# Top.net
KiCad netlist of a schematic drawn in Altium Designer
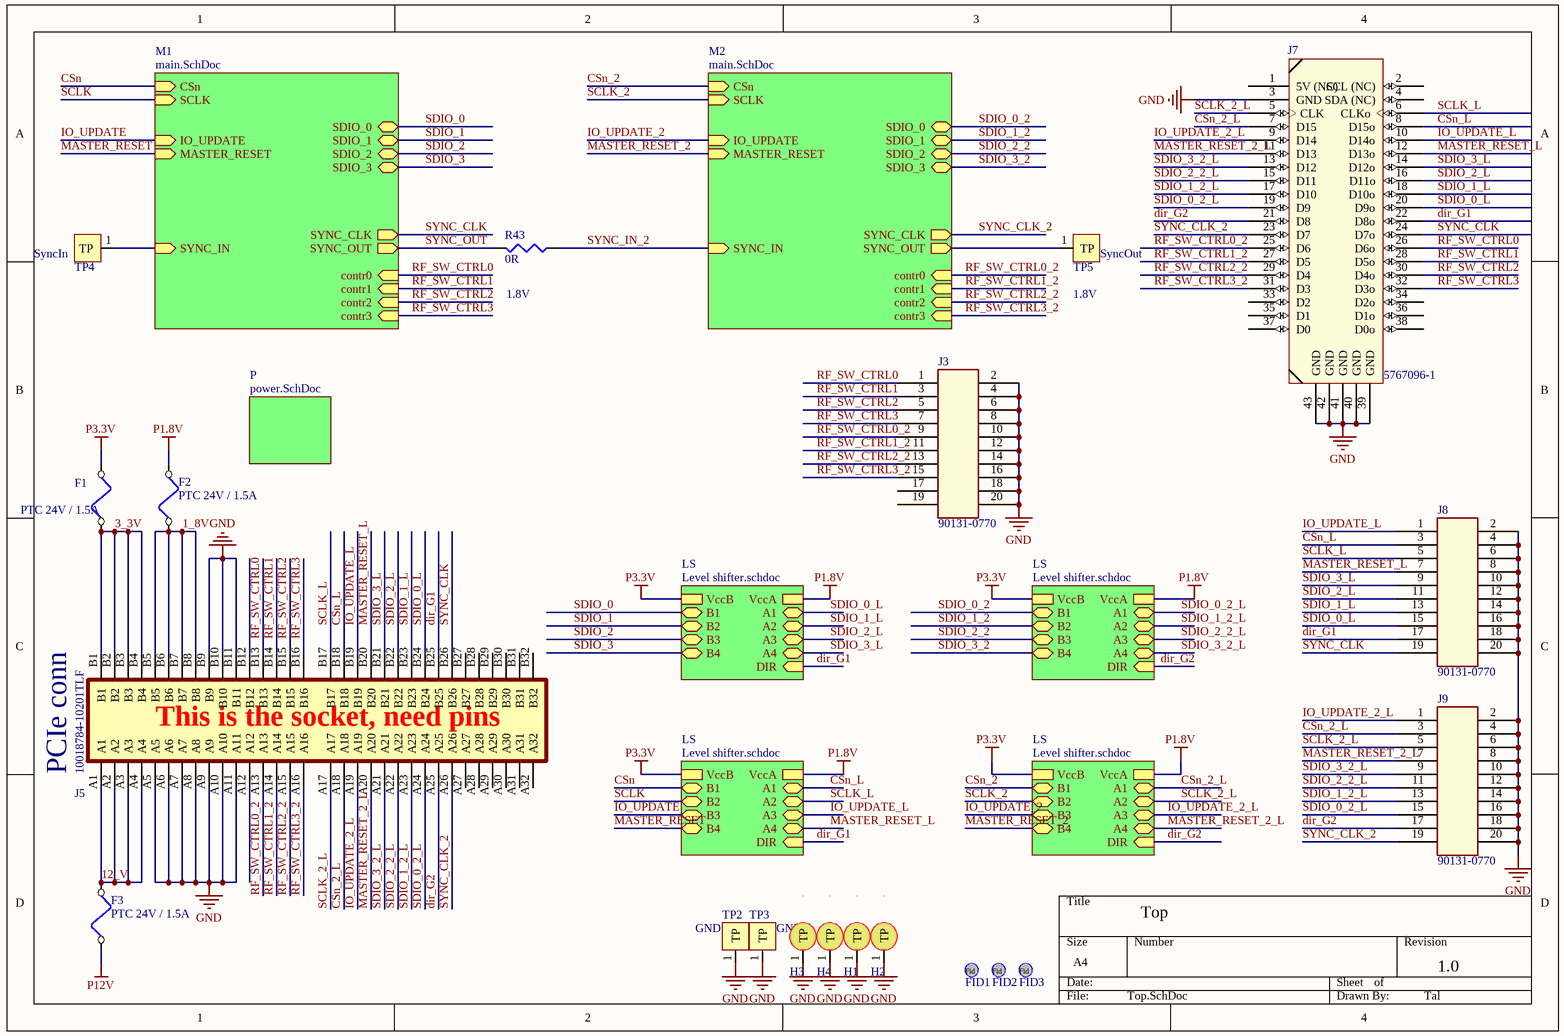
[diagram p0: Top.SchDoc]

(export (version "E")
  (design (tool "Eeschema 10.0.6"))
  (components
    (comp (ref "F1")
      (value "PTC 24V / 1.5A")
      (footprint "Landa_PCB:1812_F")
      (description "FUSE PTC 24V 1.5A POLYFUSE 1812")
      (fields
        (field (name "MANUFACTURER") "Littelfuse Inc")
        (field (name "MANUFACTURER PART NUMBER") "1812L150/24MR")
      )
      (libsource (lib "DPB_spliter") (part "1812L150/24MR"))
    )
    (comp (ref "F2")
      (value "PTC 24V / 1.5A")
      (footprint "Landa_PCB:1812_F")
      (description "FUSE PTC 24V 1.5A POLYFUSE 1812")
      (fields
        (field (name "MANUFACTURER") "Littelfuse Inc")
        (field (name "MANUFACTURER PART NUMBER") "1812L150/24MR")
      )
      (libsource (lib "DPB_spliter") (part "1812L150/24MR"))
    )
    (comp (ref "F3")
      (value "PTC 24V / 1.5A")
      (footprint "Landa_PCB:1812_F")
      (description "FUSE PTC 24V 1.5A POLYFUSE 1812")
      (fields
        (field (name "MANUFACTURER") "Littelfuse Inc")
        (field (name "MANUFACTURER PART NUMBER") "1812L150/24MR")
      )
      (libsource (lib "DPB_spliter") (part "1812L150/24MR"))
    )
    (comp (ref "FID1")
      (value "Fiducial")
      (footprint "Fiducial")
      (libsource (lib "DDS_PCB") (part "Fiducial"))
    )
    (comp (ref "FID2")
      (value "Fiducial")
      (footprint "Fiducial")
      (libsource (lib "DDS_PCB") (part "Fiducial"))
    )
    (comp (ref "FID3")
      (value "Fiducial")
      (footprint "Fiducial")
      (libsource (lib "DDS_PCB") (part "Fiducial"))
    )
    (comp (ref "H1")
      (value "Hole 3mm")
      (footprint "hole 3mm")
      (description "hole 3mm")
      (libsource (lib "L_SCH_Misc") (part "Hole 3mm"))
    )
    (comp (ref "H2")
      (value "Hole 3mm")
      (footprint "hole 3mm")
      (description "hole 3mm")
      (libsource (lib "L_SCH_Misc") (part "Hole 3mm"))
    )
    (comp (ref "H3")
      (value "Hole 3mm")
      (footprint "hole 3mm")
      (description "hole 3mm")
      (libsource (lib "L_SCH_Misc") (part "Hole 3mm"))
    )
    (comp (ref "H4")
      (value "Hole 3mm")
      (footprint "hole 3mm")
      (description "hole 3mm")
      (libsource (lib "L_SCH_Misc") (part "Hole 3mm"))
    )
    (comp (ref "J3")
      (value "90131-0770")
      (footprint "HEADER_10x2")
      (description "CONN HEADER 20 TH")
      (fields
        (field (name "MANUFACTURER") "Molex Connector Corporation")
        (field (name "MANUFACTURER PART NUMBER") "90131-0770")
      )
      (libsource (lib "L_SCH_J_Z") (part "90131-0770"))
    )
    (comp (ref "J5")
      (value "10018784-10201TLF")
      (footprint "CONN_10018784-10201TLF")
      (description "64 Position Female Connector PCI Expressâ„¢ Gold 0.039 _1.00mm_ Black")
      (fields (field (name "MF") "Amphenol ICC"))
      (libsource (lib "10018784-10201TLF") (part "10018784-10201TLF"))
    )
    (comp (ref "J7")
      (value "5767096-1")
      (footprint "MICTOR-38_PIN")
      (description "CONN MICTOR 38POS .025 VERT SMD")
      (fields
        (field (name "MANUFACTURER") "TE Connectivity")
        (field (name "MANUFACTURER PART NUMBER") "5767096-1")
      )
      (libsource (lib "L_SCH_J_Z") (part "5767096-1"))
    )
    (comp (ref "J8")
      (value "90131-0770")
      (footprint "HEADER_10x2")
      (description "CONN HEADER 20 TH")
      (fields
        (field (name "MANUFACTURER") "Molex Connector Corporation")
        (field (name "MANUFACTURER PART NUMBER") "90131-0770")
      )
      (libsource (lib "L_SCH_J_Z") (part "90131-0770"))
    )
    (comp (ref "J9")
      (value "90131-0770")
      (footprint "HEADER_10x2")
      (description "CONN HEADER 20 TH")
      (fields
        (field (name "MANUFACTURER") "Molex Connector Corporation")
        (field (name "MANUFACTURER PART NUMBER") "90131-0770")
      )
      (libsource (lib "L_SCH_J_Z") (part "90131-0770"))
    )
    (comp (ref "R43")
      (value "0R")
      (footprint "R0402")
      (description "RES 0 OHM 1/10W 1% 0402 SMD")
      (fields
        (field (name "MANUFACTURER PART NUMBER") "ERJ-2RKF1000X")
        (field (name "MANUFACTURER") "Panasonic Electronic Components")
      )
      (libsource (lib "L_SCH_R") (part "RES 100 OHM 1/10W 1% 0402 SMD"))
    )
    (comp (ref "TP2")
      (value "GND")
      (footprint "Landa_PCB:TP_2x1.8")
      (description "TP PC MINIATURE SMT")
      (fields
        (field (name "MANUFACTURER") "Keystone Electronics")
        (field (name "MANUFACTURER PART NUMBER") "5015")
      )
      (libsource (lib "") (part "TP mini_2_2"))
    )
    (comp (ref "TP3")
      (value "GND")
      (footprint "Landa_PCB:TP_2x1.8")
      (description "TP PC MINIATURE SMT")
      (fields
        (field (name "MANUFACTURER") "Keystone Electronics")
        (field (name "MANUFACTURER PART NUMBER") "5015")
      )
      (libsource (lib "DPB_spliter") (part "TP mini_1"))
    )
    (comp (ref "TP4")
      (value "SyncIn")
      (footprint "Landa_PCB:TP_2x1.8")
      (description "TP PC MINIATURE SMT")
      (fields
        (field (name "MANUFACTURER") "Keystone Electronics")
        (field (name "MANUFACTURER PART NUMBER") "5015")
      )
      (libsource (lib "DPB_spliter") (part "TP mini_2"))
    )
    (comp (ref "TP5")
      (value "SyncOut")
      (footprint "Landa_PCB:TP_2x1.8")
      (description "TP PC MINIATURE SMT")
      (fields
        (field (name "MANUFACTURER") "Keystone Electronics")
        (field (name "MANUFACTURER PART NUMBER") "5015")
      )
      (libsource (lib "") (part "TP mini_2_1"))
    )
  )
  (nets
    (net (code "1") (name "/1_8V") (class "Default")
      (node (ref "F2") (pin "1") (pinfunction "1_1") (pintype "passive"))
      (node (ref "J5") (pin "B5") (pinfunction "B5_B5") (pintype "passive"))
      (node (ref "J5") (pin "B6") (pinfunction "B6_B6") (pintype "passive"))
      (node (ref "J5") (pin "B7") (pinfunction "B7_B7") (pintype "passive"))
      (node (ref "J5") (pin "B8") (pinfunction "B8_B8") (pintype "passive"))
    )
    (net (code "2") (name "/3_3V") (class "Default")
      (node (ref "F1") (pin "1") (pinfunction "1_1") (pintype "passive"))
      (node (ref "J5") (pin "B1") (pinfunction "B1_B1") (pintype "passive"))
      (node (ref "J5") (pin "B2") (pinfunction "B2_B2") (pintype "passive"))
      (node (ref "J5") (pin "B3") (pinfunction "B3_B3") (pintype "passive"))
      (node (ref "J5") (pin "B4") (pinfunction "B4_B4") (pintype "passive"))
    )
    (net (code "3") (name "/12_V") (class "Default")
      (node (ref "F3") (pin "2") (pinfunction "2_2") (pintype "passive"))
      (node (ref "J5") (pin "A1") (pinfunction "A1_A1") (pintype "passive"))
      (node (ref "J5") (pin "A2") (pinfunction "A2_A2") (pintype "passive"))
      (node (ref "J5") (pin "A3") (pinfunction "A3_A3") (pintype "passive"))
      (node (ref "J5") (pin "A4") (pinfunction "A4_A4") (pintype "passive"))
    )
    (net (code "6") (name "/CSn_2_L") (class "Default")
      (node (ref "J5") (pin "A18") (pinfunction "A18_A18") (pintype "passive"))
      (node (ref "J7") (pin "7") (pinfunction "D15_7") (pintype "bidirectional"))
      (node (ref "J9") (pin "3") (pinfunction "3_3") (pintype "passive"))
    )
    (net (code "7") (name "/CSn_L") (class "Default")
      (node (ref "J5") (pin "B18") (pinfunction "B18_B18") (pintype "passive"))
      (node (ref "J7") (pin "8") (pinfunction "D15o_8") (pintype "bidirectional"))
      (node (ref "J8") (pin "3") (pinfunction "3_3") (pintype "passive"))
    )
    (net (code "10") (name "/IO_UPDATE_2_L") (class "Default")
      (node (ref "J5") (pin "A19") (pinfunction "A19_A19") (pintype "passive"))
      (node (ref "J7") (pin "9") (pinfunction "D14_9") (pintype "bidirectional"))
      (node (ref "J9") (pin "1") (pinfunction "1_1") (pintype "passive"))
    )
    (net (code "11") (name "/IO_UPDATE_L") (class "Default")
      (node (ref "J5") (pin "B19") (pinfunction "B19_B19") (pintype "passive"))
      (node (ref "J7") (pin "10") (pinfunction "D14o_10") (pintype "bidirectional"))
      (node (ref "J8") (pin "1") (pinfunction "1_1") (pintype "passive"))
    )
    (net (code "14") (name "/MASTER_RESET_2_L") (class "Default")
      (node (ref "J5") (pin "A20") (pinfunction "A20_A20") (pintype "passive"))
      (node (ref "J7") (pin "11") (pinfunction "D13_11") (pintype "bidirectional"))
      (node (ref "J9") (pin "7") (pinfunction "7_7") (pintype "passive"))
    )
    (net (code "15") (name "/MASTER_RESET_L") (class "Default")
      (node (ref "J5") (pin "B20") (pinfunction "B20_B20") (pintype "passive"))
      (node (ref "J7") (pin "12") (pinfunction "D13o_12") (pintype "bidirectional"))
      (node (ref "J8") (pin "7") (pinfunction "7_7") (pintype "passive"))
    )
    (net (code "16") (name "/RF_SW_CTRL0") (class "Default")
      (node (ref "J3") (pin "1") (pinfunction "1_1") (pintype "passive"))
      (node (ref "J5") (pin "B13") (pinfunction "B13_B13") (pintype "passive"))
      (node (ref "J7") (pin "26") (pinfunction "D6o_26") (pintype "bidirectional"))
    )
    (net (code "17") (name "/RF_SW_CTRL0_2") (class "Default")
      (node (ref "J3") (pin "9") (pinfunction "9_9") (pintype "passive"))
      (node (ref "J5") (pin "A13") (pinfunction "A13_A13") (pintype "passive"))
      (node (ref "J7") (pin "25") (pinfunction "D6_25") (pintype "bidirectional"))
    )
    (net (code "18") (name "/RF_SW_CTRL1") (class "Default")
      (node (ref "J3") (pin "3") (pinfunction "3_3") (pintype "passive"))
      (node (ref "J5") (pin "B14") (pinfunction "B14_B14") (pintype "passive"))
      (node (ref "J7") (pin "28") (pinfunction "D5o_28") (pintype "bidirectional"))
    )
    (net (code "19") (name "/RF_SW_CTRL1_2") (class "Default")
      (node (ref "J3") (pin "11") (pinfunction "11_11") (pintype "passive"))
      (node (ref "J5") (pin "A14") (pinfunction "A14_A14") (pintype "passive"))
      (node (ref "J7") (pin "27") (pinfunction "D5_27") (pintype "bidirectional"))
    )
    (net (code "20") (name "/RF_SW_CTRL2") (class "Default")
      (node (ref "J3") (pin "5") (pinfunction "5_5") (pintype "passive"))
      (node (ref "J5") (pin "B15") (pinfunction "B15_B15") (pintype "passive"))
      (node (ref "J7") (pin "30") (pinfunction "D4o_30") (pintype "bidirectional"))
    )
    (net (code "21") (name "/RF_SW_CTRL2_2") (class "Default")
      (node (ref "J3") (pin "13") (pinfunction "13_13") (pintype "passive"))
      (node (ref "J5") (pin "A15") (pinfunction "A15_A15") (pintype "passive"))
      (node (ref "J7") (pin "29") (pinfunction "D4_29") (pintype "bidirectional"))
    )
    (net (code "22") (name "/RF_SW_CTRL3") (class "Default")
      (node (ref "J3") (pin "7") (pinfunction "7_7") (pintype "passive"))
      (node (ref "J5") (pin "B16") (pinfunction "B16_B16") (pintype "passive"))
      (node (ref "J7") (pin "32") (pinfunction "D3o_32") (pintype "bidirectional"))
    )
    (net (code "23") (name "/RF_SW_CTRL3_2") (class "Default")
      (node (ref "J3") (pin "15") (pinfunction "15_15") (pintype "passive"))
      (node (ref "J5") (pin "A16") (pinfunction "A16_A16") (pintype "passive"))
      (node (ref "J7") (pin "31") (pinfunction "D3_31") (pintype "bidirectional"))
    )
    (net (code "26") (name "/SCLK_2_L") (class "Default")
      (node (ref "J5") (pin "A17") (pinfunction "A17_A17") (pintype "passive"))
      (node (ref "J7") (pin "5") (pinfunction "CLK_5") (pintype "bidirectional"))
      (node (ref "J9") (pin "5") (pinfunction "5_5") (pintype "passive"))
    )
    (net (code "27") (name "/SCLK_L") (class "Default")
      (node (ref "J5") (pin "B17") (pinfunction "B17_B17") (pintype "passive"))
      (node (ref "J7") (pin "6") (pinfunction "CLKo_6") (pintype "bidirectional"))
      (node (ref "J8") (pin "5") (pinfunction "5_5") (pintype "passive"))
    )
    (net (code "30") (name "/SDIO_0_2_L") (class "Default")
      (node (ref "J5") (pin "A24") (pinfunction "A24_A24") (pintype "passive"))
      (node (ref "J7") (pin "19") (pinfunction "D9_19") (pintype "bidirectional"))
      (node (ref "J9") (pin "15") (pinfunction "15_15") (pintype "passive"))
    )
    (net (code "31") (name "/SDIO_0_L") (class "Default")
      (node (ref "J5") (pin "B24") (pinfunction "B24_B24") (pintype "passive"))
      (node (ref "J7") (pin "20") (pinfunction "D9o_20") (pintype "bidirectional"))
      (node (ref "J8") (pin "15") (pinfunction "15_15") (pintype "passive"))
    )
    (net (code "34") (name "/SDIO_1_2_L") (class "Default")
      (node (ref "J5") (pin "A23") (pinfunction "A23_A23") (pintype "passive"))
      (node (ref "J7") (pin "17") (pinfunction "D10_17") (pintype "bidirectional"))
      (node (ref "J9") (pin "13") (pinfunction "13_13") (pintype "passive"))
    )
    (net (code "35") (name "/SDIO_1_L") (class "Default")
      (node (ref "J5") (pin "B23") (pinfunction "B23_B23") (pintype "passive"))
      (node (ref "J7") (pin "18") (pinfunction "D10o_18") (pintype "bidirectional"))
      (node (ref "J8") (pin "13") (pinfunction "13_13") (pintype "passive"))
    )
    (net (code "38") (name "/SDIO_2_2_L") (class "Default")
      (node (ref "J5") (pin "A22") (pinfunction "A22_A22") (pintype "passive"))
      (node (ref "J7") (pin "15") (pinfunction "D11_15") (pintype "bidirectional"))
      (node (ref "J9") (pin "11") (pinfunction "11_11") (pintype "passive"))
    )
    (net (code "39") (name "/SDIO_2_L") (class "Default")
      (node (ref "J5") (pin "B22") (pinfunction "B22_B22") (pintype "passive"))
      (node (ref "J7") (pin "16") (pinfunction "D11o_16") (pintype "bidirectional"))
      (node (ref "J8") (pin "11") (pinfunction "11_11") (pintype "passive"))
    )
    (net (code "42") (name "/SDIO_3_2_L") (class "Default")
      (node (ref "J5") (pin "A21") (pinfunction "A21_A21") (pintype "passive"))
      (node (ref "J7") (pin "13") (pinfunction "D12_13") (pintype "bidirectional"))
      (node (ref "J9") (pin "9") (pinfunction "9_9") (pintype "passive"))
    )
    (net (code "43") (name "/SDIO_3_L") (class "Default")
      (node (ref "J5") (pin "B21") (pinfunction "B21_B21") (pintype "passive"))
      (node (ref "J7") (pin "14") (pinfunction "D12o_14") (pintype "bidirectional"))
      (node (ref "J8") (pin "9") (pinfunction "9_9") (pintype "passive"))
    )
    (net (code "44") (name "/SYNC_CLK") (class "Default")
      (node (ref "J5") (pin "B26") (pinfunction "B26_B26") (pintype "passive"))
      (node (ref "J7") (pin "24") (pinfunction "D7o_24") (pintype "bidirectional"))
      (node (ref "J8") (pin "19") (pinfunction "19_19") (pintype "passive"))
    )
    (net (code "45") (name "/SYNC_CLK_2") (class "Default")
      (node (ref "J5") (pin "A26") (pinfunction "A26_A26") (pintype "passive"))
      (node (ref "J7") (pin "23") (pinfunction "D7_23") (pintype "bidirectional"))
      (node (ref "J9") (pin "19") (pinfunction "19_19") (pintype "passive"))
    )
    (net (code "46") (name "/SYNC_IN") (class "Default")
      (node (ref "TP4") (pin "1") (pinfunction "TP_1") (pintype "passive"))
    )
    (net (code "47") (name "/SYNC_IN_2") (class "Default")
      (node (ref "R43") (pin "1") (pinfunction "1_1") (pintype "passive"))
    )
    (net (code "48") (name "/SYNC_OUT") (class "Default")
      (node (ref "R43") (pin "2") (pinfunction "2_2") (pintype "passive"))
    )
    (net (code "49") (name "/SYNC_OUT_1") (class "Default")
      (node (ref "TP5") (pin "1") (pinfunction "TP_1") (pintype "passive"))
    )
    (net (code "50") (name "/dir_G1") (class "Default")
      (node (ref "J5") (pin "B25") (pinfunction "B25_B25") (pintype "passive"))
      (node (ref "J7") (pin "22") (pinfunction "D8o_22") (pintype "bidirectional"))
      (node (ref "J8") (pin "17") (pinfunction "17_17") (pintype "passive"))
    )
    (net (code "51") (name "/dir_G2") (class "Default")
      (node (ref "J5") (pin "A25") (pinfunction "A25_A25") (pintype "passive"))
      (node (ref "J7") (pin "21") (pinfunction "D8_21") (pintype "bidirectional"))
      (node (ref "J9") (pin "17") (pinfunction "17_17") (pintype "passive"))
    )
    (net (code "52") (name "GND") (class "Default")
      (node (ref "H1") (pin "1") (pinfunction "TP_1") (pintype "passive"))
      (node (ref "H2") (pin "1") (pinfunction "TP_1") (pintype "passive"))
      (node (ref "H3") (pin "1") (pinfunction "TP_1") (pintype "passive"))
      (node (ref "H4") (pin "1") (pinfunction "TP_1") (pintype "passive"))
      (node (ref "J3") (pin "10") (pinfunction "10_10") (pintype "passive"))
      (node (ref "J3") (pin "12") (pinfunction "12_12") (pintype "passive"))
      (node (ref "J3") (pin "14") (pinfunction "14_14") (pintype "passive"))
      (node (ref "J3") (pin "16") (pinfunction "16_16") (pintype "passive"))
      (node (ref "J3") (pin "18") (pinfunction "18_18") (pintype "passive"))
      (node (ref "J3") (pin "2") (pinfunction "2_2") (pintype "passive"))
      (node (ref "J3") (pin "20") (pinfunction "20_20") (pintype "passive"))
      (node (ref "J3") (pin "4") (pinfunction "4_4") (pintype "passive"))
      (node (ref "J3") (pin "6") (pinfunction "6_6") (pintype "passive"))
      (node (ref "J3") (pin "8") (pinfunction "8_8") (pintype "passive"))
      (node (ref "J5") (pin "A10") (pinfunction "A10_A10") (pintype "passive"))
      (node (ref "J5") (pin "A11") (pinfunction "A11_A11") (pintype "passive"))
      (node (ref "J5") (pin "A5") (pinfunction "A5_A5") (pintype "passive"))
      (node (ref "J5") (pin "A6") (pinfunction "A6_A6") (pintype "passive"))
      (node (ref "J5") (pin "A7") (pinfunction "A7_A7") (pintype "passive"))
      (node (ref "J5") (pin "A8") (pinfunction "A8_A8") (pintype "passive"))
      (node (ref "J5") (pin "A9") (pinfunction "A9_A9") (pintype "passive"))
      (node (ref "J5") (pin "B10") (pinfunction "B10_B10") (pintype "passive"))
      (node (ref "J5") (pin "B11") (pinfunction "B11_B11") (pintype "passive"))
      (node (ref "J5") (pin "B9") (pinfunction "B9_B9") (pintype "passive"))
      (node (ref "J7") (pin "3") (pinfunction "GND_3") (pintype "power_in"))
      (node (ref "J7") (pin "39") (pinfunction "GND_39") (pintype "power_in"))
      (node (ref "J7") (pin "40") (pinfunction "GND_40") (pintype "power_in"))
      (node (ref "J7") (pin "41") (pinfunction "GND_41") (pintype "power_in"))
      (node (ref "J7") (pin "42") (pinfunction "GND_42") (pintype "power_in"))
      (node (ref "J7") (pin "43") (pinfunction "GND_43") (pintype "power_in"))
      (node (ref "J8") (pin "10") (pinfunction "10_10") (pintype "passive"))
      (node (ref "J8") (pin "12") (pinfunction "12_12") (pintype "passive"))
      (node (ref "J8") (pin "14") (pinfunction "14_14") (pintype "passive"))
      (node (ref "J8") (pin "16") (pinfunction "16_16") (pintype "passive"))
      (node (ref "J8") (pin "18") (pinfunction "18_18") (pintype "passive"))
      (node (ref "J8") (pin "2") (pinfunction "2_2") (pintype "passive"))
      (node (ref "J8") (pin "20") (pinfunction "20_20") (pintype "passive"))
      (node (ref "J8") (pin "4") (pinfunction "4_4") (pintype "passive"))
      (node (ref "J8") (pin "6") (pinfunction "6_6") (pintype "passive"))
      (node (ref "J8") (pin "8") (pinfunction "8_8") (pintype "passive"))
      (node (ref "J9") (pin "10") (pinfunction "10_10") (pintype "passive"))
      (node (ref "J9") (pin "12") (pinfunction "12_12") (pintype "passive"))
      (node (ref "J9") (pin "14") (pinfunction "14_14") (pintype "passive"))
      (node (ref "J9") (pin "16") (pinfunction "16_16") (pintype "passive"))
      (node (ref "J9") (pin "18") (pinfunction "18_18") (pintype "passive"))
      (node (ref "J9") (pin "2") (pinfunction "2_2") (pintype "passive"))
      (node (ref "J9") (pin "20") (pinfunction "20_20") (pintype "passive"))
      (node (ref "J9") (pin "4") (pinfunction "4_4") (pintype "passive"))
      (node (ref "J9") (pin "6") (pinfunction "6_6") (pintype "passive"))
      (node (ref "J9") (pin "8") (pinfunction "8_8") (pintype "passive"))
      (node (ref "TP2") (pin "1") (pinfunction "TP_1") (pintype "passive"))
      (node (ref "TP3") (pin "1") (pinfunction "TP_1") (pintype "passive"))
    )
    (net (code "53") (name "P1.8V") (class "Default")
      (node (ref "F2") (pin "2") (pinfunction "2_2") (pintype "passive"))
    )
    (net (code "54") (name "P3.3V") (class "Default")
      (node (ref "F1") (pin "2") (pinfunction "2_2") (pintype "passive"))
    )
    (net (code "55") (name "P12V") (class "Default")
      (node (ref "F3") (pin "1") (pinfunction "1_1") (pintype "passive"))
    )
    (net (code "56") (name "unconnected-(J3-Pad17)") (class "Default")
      (node (ref "J3") (pin "17") (pinfunction "17_17") (pintype "passive"))
    )
    (net (code "57") (name "unconnected-(J3-Pad19)") (class "Default")
      (node (ref "J3") (pin "19") (pinfunction "19_19") (pintype "passive"))
    )
    (net (code "58") (name "unconnected-(J5-PadA12)") (class "Default")
      (node (ref "J5") (pin "A12") (pinfunction "A12_A12") (pintype "passive"))
    )
    (net (code "59") (name "unconnected-(J5-PadA27)") (class "Default")
      (node (ref "J5") (pin "A27") (pinfunction "A27_A27") (pintype "passive"))
    )
    (net (code "60") (name "unconnected-(J5-PadA28)") (class "Default")
      (node (ref "J5") (pin "A28") (pinfunction "A28_A28") (pintype "passive"))
    )
    (net (code "61") (name "unconnected-(J5-PadA29)") (class "Default")
      (node (ref "J5") (pin "A29") (pinfunction "A29_A29") (pintype "passive"))
    )
    (net (code "62") (name "unconnected-(J5-PadA30)") (class "Default")
      (node (ref "J5") (pin "A30") (pinfunction "A30_A30") (pintype "passive"))
    )
    (net (code "63") (name "unconnected-(J5-PadA31)") (class "Default")
      (node (ref "J5") (pin "A31") (pinfunction "A31_A31") (pintype "passive"))
    )
    (net (code "64") (name "unconnected-(J5-PadA32)") (class "Default")
      (node (ref "J5") (pin "A32") (pinfunction "A32_A32") (pintype "passive"))
    )
    (net (code "65") (name "unconnected-(J5-PadB12)") (class "Default")
      (node (ref "J5") (pin "B12") (pinfunction "B12_B12") (pintype "passive"))
    )
    (net (code "66") (name "unconnected-(J5-PadB27)") (class "Default")
      (node (ref "J5") (pin "B27") (pinfunction "B27_B27") (pintype "passive"))
    )
    (net (code "67") (name "unconnected-(J5-PadB28)") (class "Default")
      (node (ref "J5") (pin "B28") (pinfunction "B28_B28") (pintype "passive"))
    )
    (net (code "68") (name "unconnected-(J5-PadB29)") (class "Default")
      (node (ref "J5") (pin "B29") (pinfunction "B29_B29") (pintype "passive"))
    )
    (net (code "69") (name "unconnected-(J5-PadB30)") (class "Default")
      (node (ref "J5") (pin "B30") (pinfunction "B30_B30") (pintype "passive"))
    )
    (net (code "70") (name "unconnected-(J5-PadB31)") (class "Default")
      (node (ref "J5") (pin "B31") (pinfunction "B31_B31") (pintype "passive"))
    )
    (net (code "71") (name "unconnected-(J5-PadB32)") (class "Default")
      (node (ref "J5") (pin "B32") (pinfunction "B32_B32") (pintype "passive"))
    )
    (net (code "72") (name "unconnected-(J7-5V_(NC)-Pad1)") (class "Default")
      (node (ref "J7") (pin "1") (pinfunction "5V_(NC)_1") (pintype "power_in"))
    )
    (net (code "73") (name "unconnected-(J7-D0-Pad37)") (class "Default")
      (node (ref "J7") (pin "37") (pinfunction "D0_37") (pintype "bidirectional"))
    )
    (net (code "74") (name "unconnected-(J7-D0o-Pad38)") (class "Default")
      (node (ref "J7") (pin "38") (pinfunction "D0o_38") (pintype "bidirectional"))
    )
    (net (code "75") (name "unconnected-(J7-D1-Pad35)") (class "Default")
      (node (ref "J7") (pin "35") (pinfunction "D1_35") (pintype "bidirectional"))
    )
    (net (code "76") (name "unconnected-(J7-D1o-Pad36)") (class "Default")
      (node (ref "J7") (pin "36") (pinfunction "D1o_36") (pintype "bidirectional"))
    )
    (net (code "77") (name "unconnected-(J7-D2-Pad33)") (class "Default")
      (node (ref "J7") (pin "33") (pinfunction "D2_33") (pintype "bidirectional"))
    )
    (net (code "78") (name "unconnected-(J7-D2o-Pad34)") (class "Default")
      (node (ref "J7") (pin "34") (pinfunction "D2o_34") (pintype "bidirectional"))
    )
    (net (code "79") (name "unconnected-(J7-SCL_(NC)-Pad2)") (class "Default")
      (node (ref "J7") (pin "2") (pinfunction "SCL_(NC)_2") (pintype "bidirectional"))
    )
    (net (code "80") (name "unconnected-(J7-SDA_(NC)-Pad4)") (class "Default")
      (node (ref "J7") (pin "4") (pinfunction "SDA_(NC)_4") (pintype "bidirectional"))
    )
  )
)
